# Rev_A_New_Routing.net
KiCad netlist of a schematic drawn in EAGLE
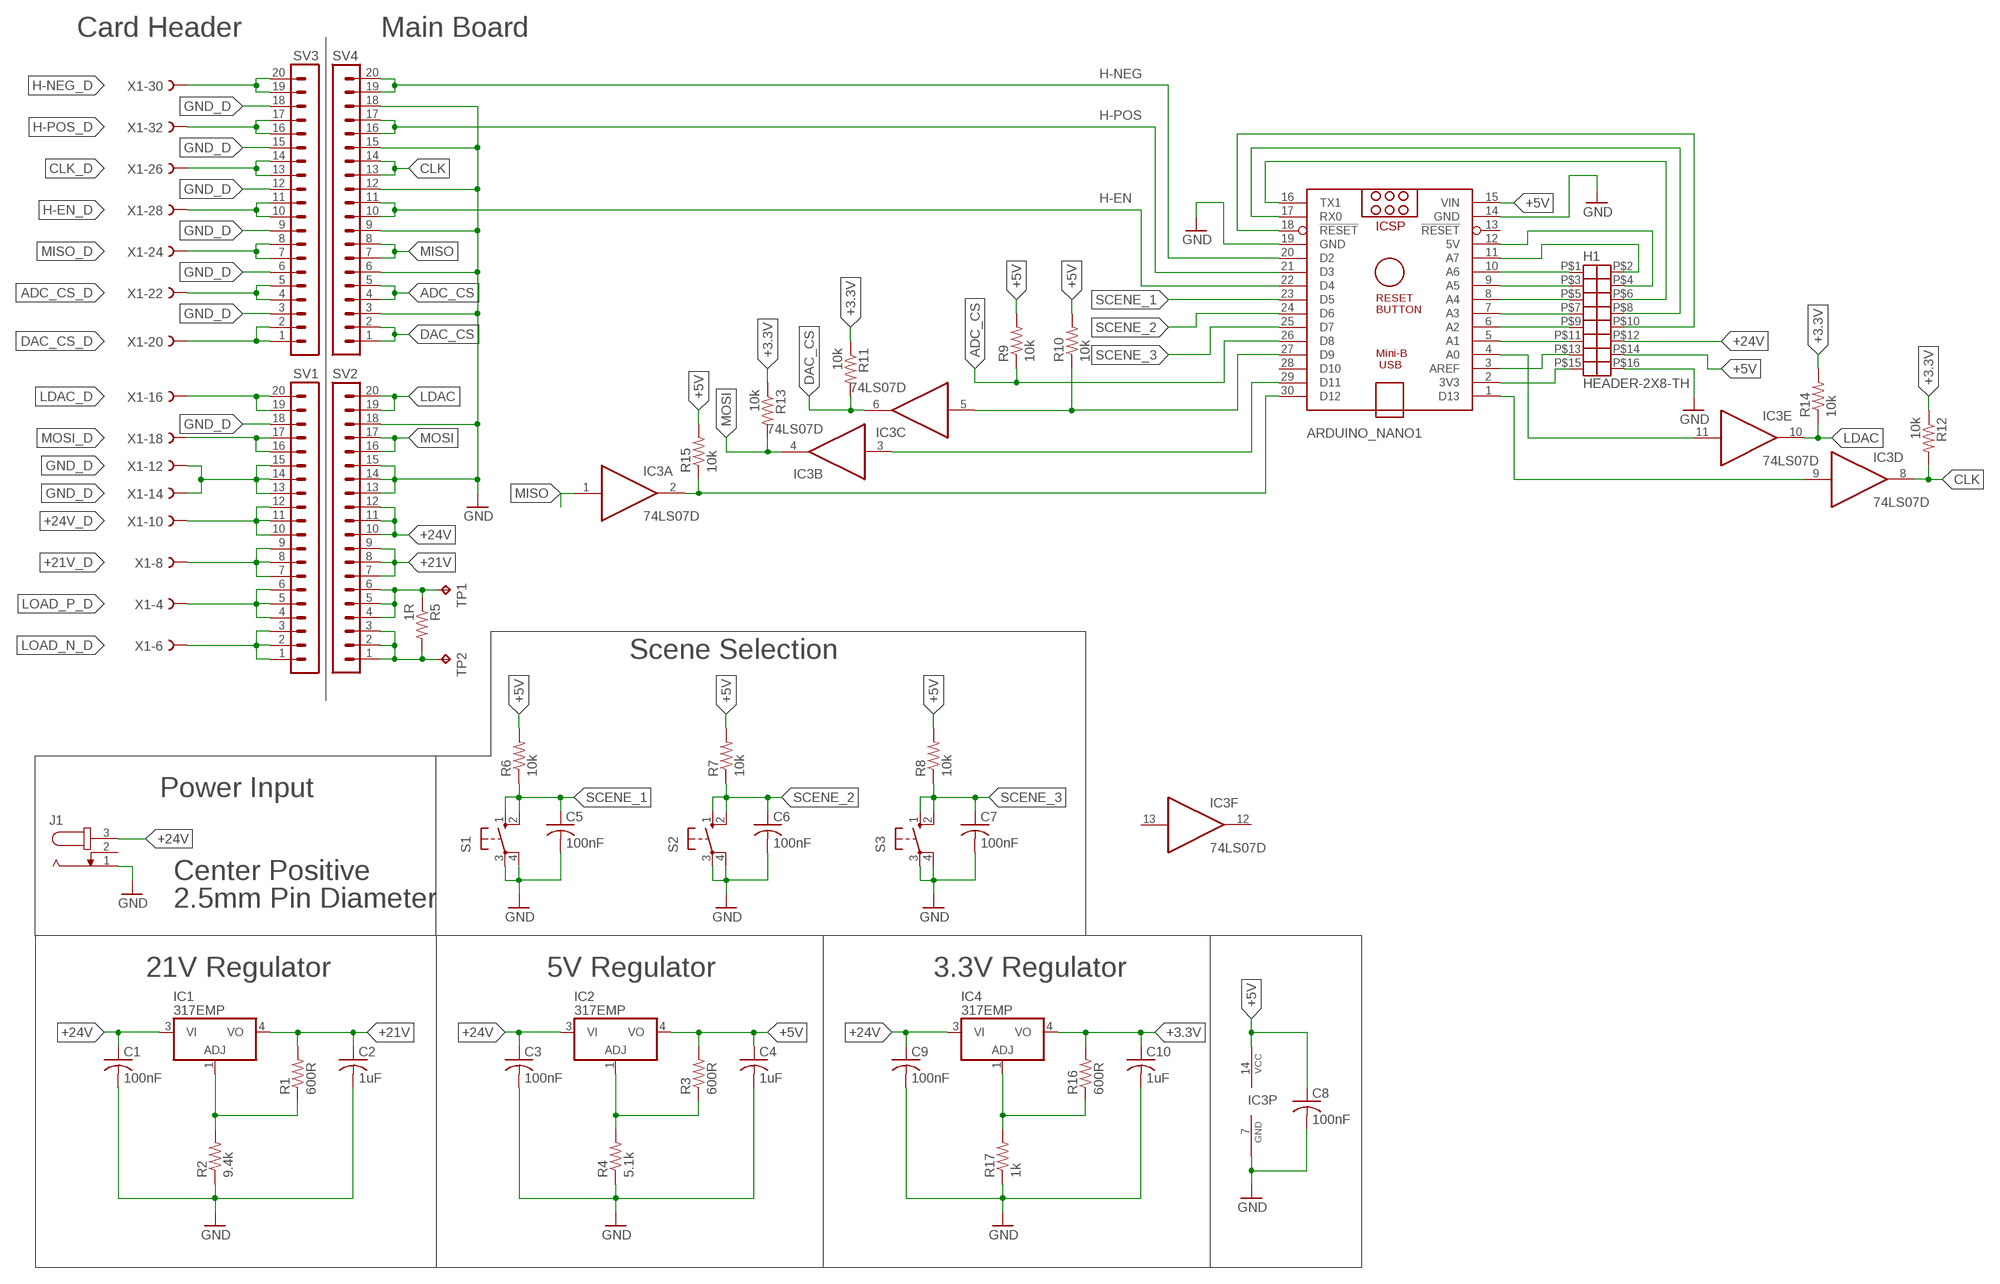
[diagram p0: schematic, sheet 1]

(export (version "E")
  (design (tool "Eeschema 10.0.6"))
  (components
    (comp (ref "ARDUINO_NANO1")
      (value "ARDUINO_NANO")
      (footprint "eagle-import:ARDUINO_NANO")
      (libsource (lib "eagle-import") (part "ARDUINO_NANO"))
    )
    (comp (ref "C1")
      (value "100nF")
      (footprint "eagle-import:C0603")
      (libsource (lib "eagle-import") (part "C-USC0603"))
    )
    (comp (ref "C2")
      (value "1uF")
      (footprint "eagle-import:C1206")
      (libsource (lib "eagle-import") (part "C-USC1206"))
    )
    (comp (ref "C3")
      (value "100nF")
      (footprint "eagle-import:C0603")
      (libsource (lib "eagle-import") (part "C-USC0603"))
    )
    (comp (ref "C4")
      (value "1uF")
      (footprint "eagle-import:C1206")
      (libsource (lib "eagle-import") (part "C-USC1206"))
    )
    (comp (ref "C5")
      (value "100nF")
      (footprint "eagle-import:C0603")
      (libsource (lib "eagle-import") (part "C-USC0603"))
    )
    (comp (ref "C6")
      (value "100nF")
      (footprint "eagle-import:C0603")
      (libsource (lib "eagle-import") (part "C-USC0603"))
    )
    (comp (ref "C7")
      (value "100nF")
      (footprint "eagle-import:C0603")
      (libsource (lib "eagle-import") (part "C-USC0603"))
    )
    (comp (ref "C8")
      (value "100nF")
      (footprint "eagle-import:C0603")
      (libsource (lib "eagle-import") (part "C-USC0603"))
    )
    (comp (ref "C9")
      (value "100nF")
      (footprint "eagle-import:C0603")
      (libsource (lib "eagle-import") (part "C-USC0603"))
    )
    (comp (ref "C10")
      (value "1uF")
      (footprint "eagle-import:C1206")
      (libsource (lib "eagle-import") (part "C-USC1206"))
    )
    (comp (ref "H1")
      (value "HEADER-2X8-TH")
      (footprint "eagle-import:HEADER-2X8-TH")
      (libsource (lib "eagle-import") (part "HEADER-2X8-TH"))
    )
    (comp (ref "IC1")
      (value "317EMP")
      (footprint "eagle-import:SOT223")
      (libsource (lib "eagle-import") (part "317EMP"))
    )
    (comp (ref "IC2")
      (value "317EMP")
      (footprint "eagle-import:SOT223")
      (libsource (lib "eagle-import") (part "317EMP"))
    )
    (comp (ref "IC3")
      (value "74LS07D")
      (footprint "eagle-import:SO14")
      (libsource (lib "eagle-import") (part "7407DLS"))
    )
    (comp (ref "IC4")
      (value "317EMP")
      (footprint "eagle-import:SOT223")
      (libsource (lib "eagle-import") (part "317EMP"))
    )
    (comp (ref "J1")
      (value "JACK-PLUG1")
      (footprint "eagle-import:SPC4078")
      (libsource (lib "eagle-import") (part "JACK-PLUG1"))
    )
    (comp (ref "R1")
      (value "600R")
      (footprint "eagle-import:R0603")
      (libsource (lib "eagle-import") (part "R-US_R0603"))
    )
    (comp (ref "R2")
      (value "9.4k")
      (footprint "eagle-import:R0603")
      (libsource (lib "eagle-import") (part "R-US_R0603"))
    )
    (comp (ref "R3")
      (value "600R")
      (footprint "eagle-import:R0603")
      (libsource (lib "eagle-import") (part "R-US_R0603"))
    )
    (comp (ref "R4")
      (value "5.1k")
      (footprint "eagle-import:R0603")
      (libsource (lib "eagle-import") (part "R-US_R0603"))
    )
    (comp (ref "R5")
      (value "1R")
      (footprint "eagle-import:R1206")
      (libsource (lib "eagle-import") (part "R-US_R1206"))
    )
    (comp (ref "R6")
      (value "10k")
      (footprint "eagle-import:R0603")
      (libsource (lib "eagle-import") (part "R-US_R0603"))
    )
    (comp (ref "R7")
      (value "10k")
      (footprint "eagle-import:R0603")
      (libsource (lib "eagle-import") (part "R-US_R0603"))
    )
    (comp (ref "R8")
      (value "10k")
      (footprint "eagle-import:R0603")
      (libsource (lib "eagle-import") (part "R-US_R0603"))
    )
    (comp (ref "R9")
      (value "10k")
      (footprint "eagle-import:R0603")
      (libsource (lib "eagle-import") (part "R-US_R0603"))
    )
    (comp (ref "R10")
      (value "10k")
      (footprint "eagle-import:R0603")
      (libsource (lib "eagle-import") (part "R-US_R0603"))
    )
    (comp (ref "R11")
      (value "10k")
      (footprint "eagle-import:R0603")
      (libsource (lib "eagle-import") (part "R-US_R0603"))
    )
    (comp (ref "R12")
      (value "10k")
      (footprint "eagle-import:R0603")
      (libsource (lib "eagle-import") (part "R-US_R0603"))
    )
    (comp (ref "R13")
      (value "10k")
      (footprint "eagle-import:R0603")
      (libsource (lib "eagle-import") (part "R-US_R0603"))
    )
    (comp (ref "R14")
      (value "10k")
      (footprint "eagle-import:R0603")
      (libsource (lib "eagle-import") (part "R-US_R0603"))
    )
    (comp (ref "R15")
      (value "10k")
      (footprint "eagle-import:R0603")
      (libsource (lib "eagle-import") (part "R-US_R0603"))
    )
    (comp (ref "R16")
      (value "600R")
      (footprint "eagle-import:R0603")
      (libsource (lib "eagle-import") (part "R-US_R0603"))
    )
    (comp (ref "R17")
      (value "1k")
      (footprint "eagle-import:R0603")
      (libsource (lib "eagle-import") (part "R-US_R0603"))
    )
    (comp (ref "S1")
      (value "10-XX")
      (footprint "eagle-import:B3F-10XX")
      (fields (field (name "MPN") "B3F-1000"))
      (libsource (lib "eagle-import") (part "10-XX"))
    )
    (comp (ref "S2")
      (value "10-XX")
      (footprint "eagle-import:B3F-10XX")
      (fields (field (name "MPN") "B3F-1000"))
      (libsource (lib "eagle-import") (part "10-XX"))
    )
    (comp (ref "S3")
      (value "10-XX")
      (footprint "eagle-import:B3F-10XX")
      (fields (field (name "MPN") "B3F-1000"))
      (libsource (lib "eagle-import") (part "10-XX"))
    )
    (comp (ref "SV1")
      (value "MA20-1")
      (footprint "eagle-import:MA20-1")
      (libsource (lib "eagle-import") (part "MA20-1"))
    )
    (comp (ref "SV2")
      (value "MA20-1W")
      (footprint "eagle-import:MA20-1W")
      (libsource (lib "eagle-import") (part "MA20-1W"))
    )
    (comp (ref "SV3")
      (value "MA20-1")
      (footprint "eagle-import:MA20-1")
      (libsource (lib "eagle-import") (part "MA20-1"))
    )
    (comp (ref "SV4")
      (value "MA20-1W")
      (footprint "eagle-import:MA20-1W")
      (libsource (lib "eagle-import") (part "MA20-1W"))
    )
    (comp (ref "TP1")
      (value "TPB2,54")
      (footprint "eagle-import:B2,54")
      (libsource (lib "eagle-import") (part "TPB2,54"))
    )
    (comp (ref "TP2")
      (value "TPB2,54")
      (footprint "eagle-import:B2,54")
      (libsource (lib "eagle-import") (part "TPB2,54"))
    )
    (comp (ref "X1")
      (value "FH15")
      (footprint "eagle-import:FH15")
      (libsource (lib "eagle-import") (part "FH15"))
    )
  )
  (nets
    (net (code "1") (name "+3.3V") (class "Default")
      (node (ref "C10") (pin "1") (pinfunction "1_1") (pintype "passive"))
      (node (ref "IC4") (pin "4") (pinfunction "VO_4") (pintype "passive"))
      (node (ref "R11") (pin "1") (pinfunction "1_1") (pintype "passive"))
      (node (ref "R12") (pin "1") (pinfunction "1_1") (pintype "passive"))
      (node (ref "R13") (pin "1") (pinfunction "1_1") (pintype "passive"))
      (node (ref "R14") (pin "2") (pinfunction "2_2") (pintype "passive"))
      (node (ref "R16") (pin "2") (pinfunction "2_2") (pintype "passive"))
    )
    (net (code "2") (name "+5V") (class "Default")
      (node (ref "ARDUINO_NANO1") (pin "15") (pinfunction "VIN_15") (pintype "power_in"))
      (node (ref "C4") (pin "1") (pinfunction "1_1") (pintype "passive"))
      (node (ref "C8") (pin "1") (pinfunction "1_1") (pintype "passive"))
      (node (ref "H1") (pin "P$14") (pinfunction "P$14_P$14") (pintype "bidirectional"))
      (node (ref "IC2") (pin "4") (pinfunction "VO_4") (pintype "passive"))
      (node (ref "IC3") (pin "14") (pinfunction "VCC_14") (pintype "power_in"))
      (node (ref "R10") (pin "2") (pinfunction "2_2") (pintype "passive"))
      (node (ref "R15") (pin "2") (pinfunction "2_2") (pintype "passive"))
      (node (ref "R3") (pin "2") (pinfunction "2_2") (pintype "passive"))
      (node (ref "R6") (pin "2") (pinfunction "2_2") (pintype "passive"))
      (node (ref "R7") (pin "2") (pinfunction "2_2") (pintype "passive"))
      (node (ref "R8") (pin "2") (pinfunction "2_2") (pintype "passive"))
      (node (ref "R9") (pin "2") (pinfunction "2_2") (pintype "passive"))
    )
    (net (code "3") (name "+21V") (class "Default")
      (node (ref "C2") (pin "1") (pinfunction "1_1") (pintype "passive"))
      (node (ref "IC1") (pin "4") (pinfunction "VO_4") (pintype "passive"))
      (node (ref "R1") (pin "2") (pinfunction "2_2") (pintype "passive"))
      (node (ref "SV2") (pin "7") (pinfunction "7_7") (pintype "passive"))
      (node (ref "SV2") (pin "8") (pinfunction "8_8") (pintype "passive"))
      (node (ref "SV2") (pin "9") (pinfunction "9_9") (pintype "passive"))
    )
    (net (code "4") (name "+21V_D") (class "Default")
      (node (ref "SV1") (pin "7") (pinfunction "7_7") (pintype "passive"))
      (node (ref "SV1") (pin "8") (pinfunction "8_8") (pintype "passive"))
      (node (ref "SV1") (pin "9") (pinfunction "9_9") (pintype "passive"))
      (node (ref "X1") (pin "8") (pinfunction "B_8") (pintype "passive"))
    )
    (net (code "5") (name "+24V") (class "Default")
      (node (ref "C1") (pin "1") (pinfunction "1_1") (pintype "passive"))
      (node (ref "C3") (pin "1") (pinfunction "1_1") (pintype "passive"))
      (node (ref "C9") (pin "1") (pinfunction "1_1") (pintype "passive"))
      (node (ref "H1") (pin "P$12") (pinfunction "P$12_P$12") (pintype "bidirectional"))
      (node (ref "IC1") (pin "3") (pinfunction "VI_3") (pintype "input"))
      (node (ref "IC2") (pin "3") (pinfunction "VI_3") (pintype "input"))
      (node (ref "IC4") (pin "3") (pinfunction "VI_3") (pintype "input"))
      (node (ref "J1") (pin "3") (pinfunction "3_3") (pintype "passive"))
      (node (ref "SV2") (pin "10") (pinfunction "10_10") (pintype "passive"))
      (node (ref "SV2") (pin "11") (pinfunction "11_11") (pintype "passive"))
      (node (ref "SV2") (pin "12") (pinfunction "12_12") (pintype "passive"))
    )
    (net (code "6") (name "+24V_D") (class "Default")
      (node (ref "SV1") (pin "10") (pinfunction "10_10") (pintype "passive"))
      (node (ref "SV1") (pin "11") (pinfunction "11_11") (pintype "passive"))
      (node (ref "SV1") (pin "12") (pinfunction "12_12") (pintype "passive"))
      (node (ref "X1") (pin "10") (pinfunction "B_10") (pintype "passive"))
    )
    (net (code "7") (name "ADC_CS") (class "Default")
      (node (ref "ARDUINO_NANO1") (pin "26") (pinfunction "D8_26") (pintype "bidirectional"))
      (node (ref "R9") (pin "1") (pinfunction "1_1") (pintype "passive"))
      (node (ref "SV4") (pin "4") (pinfunction "4_4") (pintype "passive"))
      (node (ref "SV4") (pin "5") (pinfunction "5_5") (pintype "passive"))
    )
    (net (code "8") (name "ADC_CS_D") (class "Default")
      (node (ref "SV3") (pin "4") (pinfunction "4_4") (pintype "passive"))
      (node (ref "SV3") (pin "5") (pinfunction "5_5") (pintype "passive"))
      (node (ref "X1") (pin "22") (pinfunction "B_22") (pintype "passive"))
    )
    (net (code "9") (name "CLK") (class "Default")
      (node (ref "IC3") (pin "8") (pinfunction "O_8") (pintype "open_collector"))
      (node (ref "R12") (pin "2") (pinfunction "2_2") (pintype "passive"))
      (node (ref "SV4") (pin "13") (pinfunction "13_13") (pintype "passive"))
      (node (ref "SV4") (pin "14") (pinfunction "14_14") (pintype "passive"))
    )
    (net (code "10") (name "CLK_D") (class "Default")
      (node (ref "SV3") (pin "13") (pinfunction "13_13") (pintype "passive"))
      (node (ref "SV3") (pin "14") (pinfunction "14_14") (pintype "passive"))
      (node (ref "X1") (pin "26") (pinfunction "B_26") (pintype "passive"))
    )
    (net (code "11") (name "DAC_CS") (class "Default")
      (node (ref "IC3") (pin "6") (pinfunction "O_6") (pintype "open_collector"))
      (node (ref "R11") (pin "2") (pinfunction "2_2") (pintype "passive"))
      (node (ref "SV4") (pin "1") (pinfunction "1_1") (pintype "passive"))
      (node (ref "SV4") (pin "2") (pinfunction "2_2") (pintype "passive"))
    )
    (net (code "12") (name "DAC_CS_D") (class "Default")
      (node (ref "SV3") (pin "1") (pinfunction "1_1") (pintype "passive"))
      (node (ref "SV3") (pin "2") (pinfunction "2_2") (pintype "passive"))
      (node (ref "X1") (pin "20") (pinfunction "B_20") (pintype "passive"))
    )
    (net (code "13") (name "GND") (class "Default")
      (node (ref "ARDUINO_NANO1") (pin "14") (pinfunction "GND_14") (pintype "power_in"))
      (node (ref "ARDUINO_NANO1") (pin "19") (pinfunction "GND_19") (pintype "power_in"))
      (node (ref "C1") (pin "2") (pinfunction "2_2") (pintype "passive"))
      (node (ref "C10") (pin "2") (pinfunction "2_2") (pintype "passive"))
      (node (ref "C2") (pin "2") (pinfunction "2_2") (pintype "passive"))
      (node (ref "C3") (pin "2") (pinfunction "2_2") (pintype "passive"))
      (node (ref "C4") (pin "2") (pinfunction "2_2") (pintype "passive"))
      (node (ref "C5") (pin "2") (pinfunction "2_2") (pintype "passive"))
      (node (ref "C6") (pin "2") (pinfunction "2_2") (pintype "passive"))
      (node (ref "C7") (pin "2") (pinfunction "2_2") (pintype "passive"))
      (node (ref "C8") (pin "2") (pinfunction "2_2") (pintype "passive"))
      (node (ref "C9") (pin "2") (pinfunction "2_2") (pintype "passive"))
      (node (ref "H1") (pin "P$16") (pinfunction "P$16_P$16") (pintype "bidirectional"))
      (node (ref "IC3") (pin "7") (pinfunction "GND_7") (pintype "power_in"))
      (node (ref "J1") (pin "1") (pinfunction "1_1") (pintype "passive"))
      (node (ref "R17") (pin "1") (pinfunction "1_1") (pintype "passive"))
      (node (ref "R2") (pin "1") (pinfunction "1_1") (pintype "passive"))
      (node (ref "R4") (pin "1") (pinfunction "1_1") (pintype "passive"))
      (node (ref "S1") (pin "3") (pinfunction "P_3") (pintype "passive"))
      (node (ref "S1") (pin "4") (pinfunction "P1_4") (pintype "passive"))
      (node (ref "S2") (pin "3") (pinfunction "P_3") (pintype "passive"))
      (node (ref "S2") (pin "4") (pinfunction "P1_4") (pintype "passive"))
      (node (ref "S3") (pin "3") (pinfunction "P_3") (pintype "passive"))
      (node (ref "S3") (pin "4") (pinfunction "P1_4") (pintype "passive"))
      (node (ref "SV2") (pin "13") (pinfunction "13_13") (pintype "passive"))
      (node (ref "SV2") (pin "14") (pinfunction "14_14") (pintype "passive"))
      (node (ref "SV2") (pin "15") (pinfunction "15_15") (pintype "passive"))
      (node (ref "SV2") (pin "18") (pinfunction "18_18") (pintype "passive"))
      (node (ref "SV4") (pin "12") (pinfunction "12_12") (pintype "passive"))
      (node (ref "SV4") (pin "15") (pinfunction "15_15") (pintype "passive"))
      (node (ref "SV4") (pin "18") (pinfunction "18_18") (pintype "passive"))
      (node (ref "SV4") (pin "3") (pinfunction "3_3") (pintype "passive"))
      (node (ref "SV4") (pin "6") (pinfunction "6_6") (pintype "passive"))
      (node (ref "SV4") (pin "9") (pinfunction "9_9") (pintype "passive"))
    )
    (net (code "14") (name "GND_D") (class "Default")
      (node (ref "SV1") (pin "13") (pinfunction "13_13") (pintype "passive"))
      (node (ref "SV1") (pin "14") (pinfunction "14_14") (pintype "passive"))
      (node (ref "SV1") (pin "15") (pinfunction "15_15") (pintype "passive"))
      (node (ref "SV1") (pin "18") (pinfunction "18_18") (pintype "passive"))
      (node (ref "SV3") (pin "12") (pinfunction "12_12") (pintype "passive"))
      (node (ref "SV3") (pin "15") (pinfunction "15_15") (pintype "passive"))
      (node (ref "SV3") (pin "18") (pinfunction "18_18") (pintype "passive"))
      (node (ref "SV3") (pin "3") (pinfunction "3_3") (pintype "passive"))
      (node (ref "SV3") (pin "6") (pinfunction "6_6") (pintype "passive"))
      (node (ref "SV3") (pin "9") (pinfunction "9_9") (pintype "passive"))
      (node (ref "X1") (pin "12") (pinfunction "B_12") (pintype "passive"))
      (node (ref "X1") (pin "14") (pinfunction "B_14") (pintype "passive"))
    )
    (net (code "15") (name "H-EN_D") (class "Default")
      (node (ref "SV3") (pin "10") (pinfunction "10_10") (pintype "passive"))
      (node (ref "SV3") (pin "11") (pinfunction "11_11") (pintype "passive"))
      (node (ref "X1") (pin "28") (pinfunction "B_28") (pintype "passive"))
    )
    (net (code "16") (name "H-NEG_D") (class "Default")
      (node (ref "SV3") (pin "19") (pinfunction "19_19") (pintype "passive"))
      (node (ref "SV3") (pin "20") (pinfunction "20_20") (pintype "passive"))
      (node (ref "X1") (pin "30") (pinfunction "B_30") (pintype "passive"))
    )
    (net (code "17") (name "H-POS_D") (class "Default")
      (node (ref "SV3") (pin "16") (pinfunction "16_16") (pintype "passive"))
      (node (ref "SV3") (pin "17") (pinfunction "17_17") (pintype "passive"))
      (node (ref "X1") (pin "32") (pinfunction "B_32") (pintype "passive"))
    )
    (net (code "18") (name "LDAC") (class "Default")
      (node (ref "IC3") (pin "10") (pinfunction "O_10") (pintype "open_collector"))
      (node (ref "R14") (pin "1") (pinfunction "1_1") (pintype "passive"))
      (node (ref "SV2") (pin "19") (pinfunction "19_19") (pintype "passive"))
      (node (ref "SV2") (pin "20") (pinfunction "20_20") (pintype "passive"))
    )
    (net (code "19") (name "LDAC_D") (class "Default")
      (node (ref "SV1") (pin "19") (pinfunction "19_19") (pintype "passive"))
      (node (ref "SV1") (pin "20") (pinfunction "20_20") (pintype "passive"))
      (node (ref "X1") (pin "16") (pinfunction "B_16") (pintype "passive"))
    )
    (net (code "20") (name "LOAD_N_D") (class "Default")
      (node (ref "SV1") (pin "1") (pinfunction "1_1") (pintype "passive"))
      (node (ref "SV1") (pin "2") (pinfunction "2_2") (pintype "passive"))
      (node (ref "SV1") (pin "3") (pinfunction "3_3") (pintype "passive"))
      (node (ref "X1") (pin "6") (pinfunction "B_6") (pintype "passive"))
    )
    (net (code "21") (name "LOAD_P_D") (class "Default")
      (node (ref "SV1") (pin "4") (pinfunction "4_4") (pintype "passive"))
      (node (ref "SV1") (pin "5") (pinfunction "5_5") (pintype "passive"))
      (node (ref "SV1") (pin "6") (pinfunction "6_6") (pintype "passive"))
      (node (ref "X1") (pin "4") (pinfunction "B_4") (pintype "passive"))
    )
    (net (code "22") (name "MISO") (class "Default")
      (node (ref "IC3") (pin "1") (pinfunction "I_1") (pintype "input"))
      (node (ref "SV4") (pin "7") (pinfunction "7_7") (pintype "passive"))
      (node (ref "SV4") (pin "8") (pinfunction "8_8") (pintype "passive"))
    )
    (net (code "23") (name "MISO_D") (class "Default")
      (node (ref "SV3") (pin "7") (pinfunction "7_7") (pintype "passive"))
      (node (ref "SV3") (pin "8") (pinfunction "8_8") (pintype "passive"))
      (node (ref "X1") (pin "24") (pinfunction "B_24") (pintype "passive"))
    )
    (net (code "24") (name "MOSI") (class "Default")
      (node (ref "IC3") (pin "4") (pinfunction "O_4") (pintype "open_collector"))
      (node (ref "R13") (pin "2") (pinfunction "2_2") (pintype "passive"))
      (node (ref "SV2") (pin "16") (pinfunction "16_16") (pintype "passive"))
      (node (ref "SV2") (pin "17") (pinfunction "17_17") (pintype "passive"))
    )
    (net (code "25") (name "MOSI_D") (class "Default")
      (node (ref "SV1") (pin "16") (pinfunction "16_16") (pintype "passive"))
      (node (ref "SV1") (pin "17") (pinfunction "17_17") (pintype "passive"))
      (node (ref "X1") (pin "18") (pinfunction "B_18") (pintype "passive"))
    )
    (net (code "26") (name "Net-(ARDUINO_NANO1-3V3)") (class "Default")
      (node (ref "ARDUINO_NANO1") (pin "2") (pinfunction "3V3_2") (pintype "output"))
      (node (ref "H1") (pin "P$15") (pinfunction "P$15_P$15") (pintype "bidirectional"))
    )
    (net (code "27") (name "Net-(ARDUINO_NANO1-5V)") (class "Default")
      (node (ref "ARDUINO_NANO1") (pin "12") (pinfunction "5V_12") (pintype "power_in"))
      (node (ref "H1") (pin "P$4") (pinfunction "P$4_P$4") (pintype "bidirectional"))
    )
    (net (code "28") (name "Net-(ARDUINO_NANO1-A0)") (class "Default")
      (node (ref "ARDUINO_NANO1") (pin "4") (pinfunction "A0_4") (pintype "bidirectional"))
      (node (ref "IC3") (pin "11") (pinfunction "I_11") (pintype "input"))
    )
    (net (code "29") (name "Net-(ARDUINO_NANO1-A1)") (class "Default")
      (node (ref "ARDUINO_NANO1") (pin "5") (pinfunction "A1_5") (pintype "bidirectional"))
      (node (ref "H1") (pin "P$11") (pinfunction "P$11_P$11") (pintype "bidirectional"))
    )
    (net (code "30") (name "Net-(ARDUINO_NANO1-A2)") (class "Default")
      (node (ref "ARDUINO_NANO1") (pin "6") (pinfunction "A2_6") (pintype "bidirectional"))
      (node (ref "H1") (pin "P$9") (pinfunction "P$9_P$9") (pintype "bidirectional"))
    )
    (net (code "31") (name "Net-(ARDUINO_NANO1-A3)") (class "Default")
      (node (ref "ARDUINO_NANO1") (pin "7") (pinfunction "A3_7") (pintype "bidirectional"))
      (node (ref "H1") (pin "P$7") (pinfunction "P$7_P$7") (pintype "bidirectional"))
    )
    (net (code "32") (name "Net-(ARDUINO_NANO1-A4)") (class "Default")
      (node (ref "ARDUINO_NANO1") (pin "8") (pinfunction "A4_8") (pintype "bidirectional"))
      (node (ref "H1") (pin "P$5") (pinfunction "P$5_P$5") (pintype "bidirectional"))
    )
    (net (code "33") (name "Net-(ARDUINO_NANO1-A5)") (class "Default")
      (node (ref "ARDUINO_NANO1") (pin "9") (pinfunction "A5_9") (pintype "bidirectional"))
      (node (ref "H1") (pin "P$3") (pinfunction "P$3_P$3") (pintype "bidirectional"))
    )
    (net (code "34") (name "Net-(ARDUINO_NANO1-A6)") (class "Default")
      (node (ref "ARDUINO_NANO1") (pin "10") (pinfunction "A6_10") (pintype "bidirectional"))
      (node (ref "H1") (pin "P$1") (pinfunction "P$1_P$1") (pintype "bidirectional"))
    )
    (net (code "35") (name "Net-(ARDUINO_NANO1-A7)") (class "Default")
      (node (ref "ARDUINO_NANO1") (pin "11") (pinfunction "A7_11") (pintype "bidirectional"))
      (node (ref "H1") (pin "P$2") (pinfunction "P$2_P$2") (pintype "bidirectional"))
    )
    (net (code "36") (name "Net-(ARDUINO_NANO1-AREF)") (class "Default")
      (node (ref "ARDUINO_NANO1") (pin "3") (pinfunction "AREF_3") (pintype "input"))
      (node (ref "H1") (pin "P$13") (pinfunction "P$13_P$13") (pintype "bidirectional"))
    )
    (net (code "37") (name "Net-(ARDUINO_NANO1-D2)") (class "Default")
      (node (ref "ARDUINO_NANO1") (pin "20") (pinfunction "D2_20") (pintype "bidirectional"))
      (node (ref "SV4") (pin "19") (pinfunction "19_19") (pintype "passive"))
      (node (ref "SV4") (pin "20") (pinfunction "20_20") (pintype "passive"))
    )
    (net (code "38") (name "Net-(ARDUINO_NANO1-D3)") (class "Default")
      (node (ref "ARDUINO_NANO1") (pin "21") (pinfunction "D3_21") (pintype "bidirectional"))
      (node (ref "SV4") (pin "16") (pinfunction "16_16") (pintype "passive"))
      (node (ref "SV4") (pin "17") (pinfunction "17_17") (pintype "passive"))
    )
    (net (code "39") (name "Net-(ARDUINO_NANO1-D4)") (class "Default")
      (node (ref "ARDUINO_NANO1") (pin "22") (pinfunction "D4_22") (pintype "bidirectional"))
      (node (ref "SV4") (pin "10") (pinfunction "10_10") (pintype "passive"))
      (node (ref "SV4") (pin "11") (pinfunction "11_11") (pintype "passive"))
    )
    (net (code "40") (name "Net-(ARDUINO_NANO1-D9)") (class "Default")
      (node (ref "ARDUINO_NANO1") (pin "27") (pinfunction "D9_27") (pintype "bidirectional"))
      (node (ref "IC3") (pin "5") (pinfunction "I_5") (pintype "input"))
      (node (ref "R10") (pin "1") (pinfunction "1_1") (pintype "passive"))
    )
    (net (code "41") (name "Net-(ARDUINO_NANO1-D11)") (class "Default")
      (node (ref "ARDUINO_NANO1") (pin "29") (pinfunction "D11_29") (pintype "bidirectional"))
      (node (ref "IC3") (pin "3") (pinfunction "I_3") (pintype "input"))
    )
    (net (code "42") (name "Net-(ARDUINO_NANO1-D12)") (class "Default")
      (node (ref "ARDUINO_NANO1") (pin "30") (pinfunction "D12_30") (pintype "bidirectional"))
      (node (ref "IC3") (pin "2") (pinfunction "O_2") (pintype "open_collector"))
      (node (ref "R15") (pin "1") (pinfunction "1_1") (pintype "passive"))
    )
    (net (code "43") (name "Net-(ARDUINO_NANO1-D13)") (class "Default")
      (node (ref "ARDUINO_NANO1") (pin "1") (pinfunction "D13_1") (pintype "bidirectional"))
      (node (ref "IC3") (pin "9") (pinfunction "I_9") (pintype "input"))
    )
    (net (code "44") (name "Net-(ARDUINO_NANO1-RX0)") (class "Default")
      (node (ref "ARDUINO_NANO1") (pin "17") (pinfunction "RX0_17") (pintype "bidirectional"))
      (node (ref "H1") (pin "P$8") (pinfunction "P$8_P$8") (pintype "bidirectional"))
    )
    (net (code "45") (name "Net-(ARDUINO_NANO1-TX1)") (class "Default")
      (node (ref "ARDUINO_NANO1") (pin "16") (pinfunction "TX1_16") (pintype "bidirectional"))
      (node (ref "H1") (pin "P$6") (pinfunction "P$6_P$6") (pintype "bidirectional"))
    )
    (net (code "46") (name "Net-(ARDUINO_NANO1-~{RESET}-Pad18)") (class "Default")
      (node (ref "ARDUINO_NANO1") (pin "18") (pinfunction "~{RESET}_18") (pintype "input"))
      (node (ref "H1") (pin "P$10") (pinfunction "P$10_P$10") (pintype "bidirectional"))
    )
    (net (code "47") (name "Net-(IC1-ADJ)") (class "Default")
      (node (ref "IC1") (pin "1") (pinfunction "ADJ_1") (pintype "input"))
      (node (ref "R1") (pin "1") (pinfunction "1_1") (pintype "passive"))
      (node (ref "R2") (pin "2") (pinfunction "2_2") (pintype "passive"))
    )
    (net (code "48") (name "Net-(IC2-ADJ)") (class "Default")
      (node (ref "IC2") (pin "1") (pinfunction "ADJ_1") (pintype "input"))
      (node (ref "R3") (pin "1") (pinfunction "1_1") (pintype "passive"))
      (node (ref "R4") (pin "2") (pinfunction "2_2") (pintype "passive"))
    )
    (net (code "49") (name "Net-(IC4-ADJ)") (class "Default")
      (node (ref "IC4") (pin "1") (pinfunction "ADJ_1") (pintype "input"))
      (node (ref "R16") (pin "1") (pinfunction "1_1") (pintype "passive"))
      (node (ref "R17") (pin "2") (pinfunction "2_2") (pintype "passive"))
    )
    (net (code "50") (name "Net-(R5-Pad1)") (class "Default")
      (node (ref "R5") (pin "1") (pinfunction "1_1") (pintype "passive"))
      (node (ref "SV2") (pin "4") (pinfunction "4_4") (pintype "passive"))
      (node (ref "SV2") (pin "5") (pinfunction "5_5") (pintype "passive"))
      (node (ref "SV2") (pin "6") (pinfunction "6_6") (pintype "passive"))
      (node (ref "TP1") (pin "TP") (pinfunction "TP_TP") (pintype "input"))
    )
    (net (code "51") (name "Net-(R5-Pad2)") (class "Default")
      (node (ref "R5") (pin "2") (pinfunction "2_2") (pintype "passive"))
      (node (ref "SV2") (pin "1") (pinfunction "1_1") (pintype "passive"))
      (node (ref "SV2") (pin "2") (pinfunction "2_2") (pintype "passive"))
      (node (ref "SV2") (pin "3") (pinfunction "3_3") (pintype "passive"))
      (node (ref "TP2") (pin "TP") (pinfunction "TP_TP") (pintype "input"))
    )
    (net (code "52") (name "SCENE_1") (class "Default")
      (node (ref "ARDUINO_NANO1") (pin "23") (pinfunction "D5_23") (pintype "bidirectional"))
      (node (ref "C5") (pin "1") (pinfunction "1_1") (pintype "passive"))
      (node (ref "R6") (pin "1") (pinfunction "1_1") (pintype "passive"))
      (node (ref "S1") (pin "1") (pinfunction "S_1") (pintype "passive"))
      (node (ref "S1") (pin "2") (pinfunction "S1_2") (pintype "passive"))
    )
    (net (code "53") (name "SCENE_2") (class "Default")
      (node (ref "ARDUINO_NANO1") (pin "24") (pinfunction "D6_24") (pintype "bidirectional"))
      (node (ref "C6") (pin "1") (pinfunction "1_1") (pintype "passive"))
      (node (ref "R7") (pin "1") (pinfunction "1_1") (pintype "passive"))
      (node (ref "S2") (pin "1") (pinfunction "S_1") (pintype "passive"))
      (node (ref "S2") (pin "2") (pinfunction "S1_2") (pintype "passive"))
    )
    (net (code "54") (name "SCENE_3") (class "Default")
      (node (ref "ARDUINO_NANO1") (pin "25") (pinfunction "D7_25") (pintype "bidirectional"))
      (node (ref "C7") (pin "1") (pinfunction "1_1") (pintype "passive"))
      (node (ref "R8") (pin "1") (pinfunction "1_1") (pintype "passive"))
      (node (ref "S3") (pin "1") (pinfunction "S_1") (pintype "passive"))
      (node (ref "S3") (pin "2") (pinfunction "S1_2") (pintype "passive"))
    )
    (net (code "55") (name "unconnected-(ARDUINO_NANO1-D10-Pad28)") (class "Default")
      (node (ref "ARDUINO_NANO1") (pin "28") (pinfunction "D10_28") (pintype "bidirectional"))
    )
    (net (code "56") (name "unconnected-(ARDUINO_NANO1-~{RESET}-Pad13)") (class "Default")
      (node (ref "ARDUINO_NANO1") (pin "13") (pinfunction "~{RESET}_13") (pintype "input"))
    )
    (net (code "57") (name "unconnected-(IC3F-I-Pad13)") (class "Default")
      (node (ref "IC3") (pin "13") (pinfunction "I_13") (pintype "input"))
    )
    (net (code "58") (name "unconnected-(IC3F-O-Pad12)") (class "Default")
      (node (ref "IC3") (pin "12") (pinfunction "O_12") (pintype "open_collector"))
    )
    (net (code "59") (name "unconnected-(J1-Pad2)") (class "Default")
      (node (ref "J1") (pin "2") (pinfunction "2_2") (pintype "passive"))
    )
  )
)
